# Sub-A_BPF.net
KiCad netlist of a schematic drawn in Altium Designer
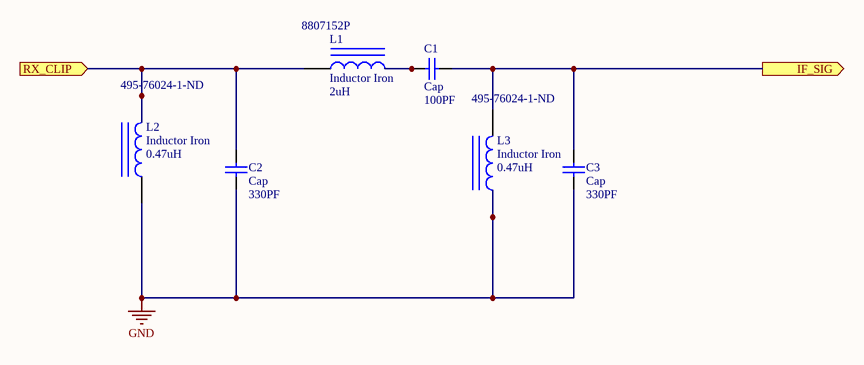
[diagram p0: Sub-A_BPF.SchDoc]

(export (version "E")
  (design (tool "Eeschema 10.0.6"))
  (components
    (comp (ref "C1")
      (value "Cap")
      (footprint "RADIAL-0.1")
      (description "Capacitor")
      (fields
        (field (name "ALTIUM_VALUE") "100PF")
        (field (name "MANUFACTURER PART NUMBER") "K101K15C0GF53L2")
        (field (name "PUBLISHER") "Altium Limited")
      )
      (libsource (lib "ECE295-Capacitors-TH") (part "CAP CER 100PF 50V C0G/NP0 RADIAL"))
    )
    (comp (ref "C2")
      (value "Cap")
      (footprint "RADIAL-0.1")
      (description "Capacitor")
      (fields
        (field (name "ALTIUM_VALUE") "330PF")
        (field (name "MANUFACTURER PART NUMBER") "K331K15X7RF53L2")
        (field (name "PUBLISHER") "Altium Limited")
      )
      (libsource (lib "ECE295-Capacitors-TH") (part "CAP CER 330PF 50V X7R RADIAL"))
    )
    (comp (ref "C3")
      (value "Cap")
      (footprint "RADIAL-0.1")
      (description "Capacitor")
      (fields
        (field (name "ALTIUM_VALUE") "330PF")
        (field (name "MANUFACTURER PART NUMBER") "K331K15X7RF53L2")
        (field (name "PUBLISHER") "Altium Limited")
      )
      (libsource (lib "ECE295-Capacitors-TH") (part "CAP CER 330PF 50V X7R RADIAL"))
    )
    (comp (ref "L1")
      (value "Inductor Iron")
      (footprint "AXIAL-0.9")
      (description "VHF-CHOKE                 2uH      4A")
      (fields
        (field (name "ALTIUM_VALUE") "2uH")
        (field (name "SUPPLIER PART NUMBER 1") "8807152P")
        (field (name "MANUFACTURER") "TDK EPCOS")
        (field (name "MANUFACTURER PART NUMBER") "B82132A5402M")
        (field (name "PUBLISHER") "Altium Limited")
      )
      (libsource (lib "Miscellaneous Devices") (part "Inductor Iron"))
    )
    (comp (ref "L2")
      (value "Inductor Iron")
      (footprint "AXIAL-0.9")
      (description "Fixed Ind 470NH 5A 27 Mohm Th")
      (fields
        (field (name "ALTIUM_VALUE") "0.47uH")
        (field (name "SUPPLIER PART NUMBER 1") "495-76024-1-ND")
        (field (name "MANUFACTURER") "TDK EPCOS")
        (field (name "MANUFACTURER PART NUMBER") "B78108E1471M009")
        (field (name "PUBLISHER") "Altium Limited")
      )
      (libsource (lib "Miscellaneous Devices") (part "Inductor Iron"))
    )
    (comp (ref "L3")
      (value "Inductor Iron")
      (footprint "AXIAL-0.9")
      (description "Fixed Ind 470NH 5A 27 Mohm Th")
      (fields
        (field (name "ALTIUM_VALUE") "0.47uH")
        (field (name "SUPPLIER PART NUMBER 1") "495-76024-1-ND")
        (field (name "MANUFACTURER") "TDK EPCOS")
        (field (name "MANUFACTURER PART NUMBER") "B78108E1471M009")
        (field (name "PUBLISHER") "Altium Limited")
      )
      (libsource (lib "Miscellaneous Devices") (part "Inductor Iron"))
    )
  )
  (nets
    (net (code "1") (name "/IF_SIG") (class "Default")
      (node (ref "C1") (pin "2") (pinfunction "2_2") (pintype "passive"))
      (node (ref "C3") (pin "2") (pinfunction "2_2") (pintype "passive"))
      (node (ref "L3") (pin "2") (pinfunction "2_2") (pintype "passive"))
    )
    (net (code "2") (name "/RX_CLIP") (class "Default")
      (node (ref "C2") (pin "2") (pinfunction "2_2") (pintype "passive"))
      (node (ref "L1") (pin "1") (pinfunction "1_1") (pintype "passive"))
      (node (ref "L2") (pin "2") (pinfunction "2_2") (pintype "passive"))
    )
    (net (code "3") (name "GND") (class "Default")
      (node (ref "C2") (pin "1") (pinfunction "1_1") (pintype "passive"))
      (node (ref "C3") (pin "1") (pinfunction "1_1") (pintype "passive"))
      (node (ref "L2") (pin "1") (pinfunction "1_1") (pintype "passive"))
      (node (ref "L3") (pin "1") (pinfunction "1_1") (pintype "passive"))
    )
    (net (code "4") (name "Net-(C1-Pad1)") (class "Default")
      (node (ref "C1") (pin "1") (pinfunction "1_1") (pintype "passive"))
      (node (ref "L1") (pin "2") (pinfunction "2_2") (pintype "passive"))
    )
  )
)
